# 10-RJ45_Protection.net
KiCad netlist of a schematic drawn in Altium Designer
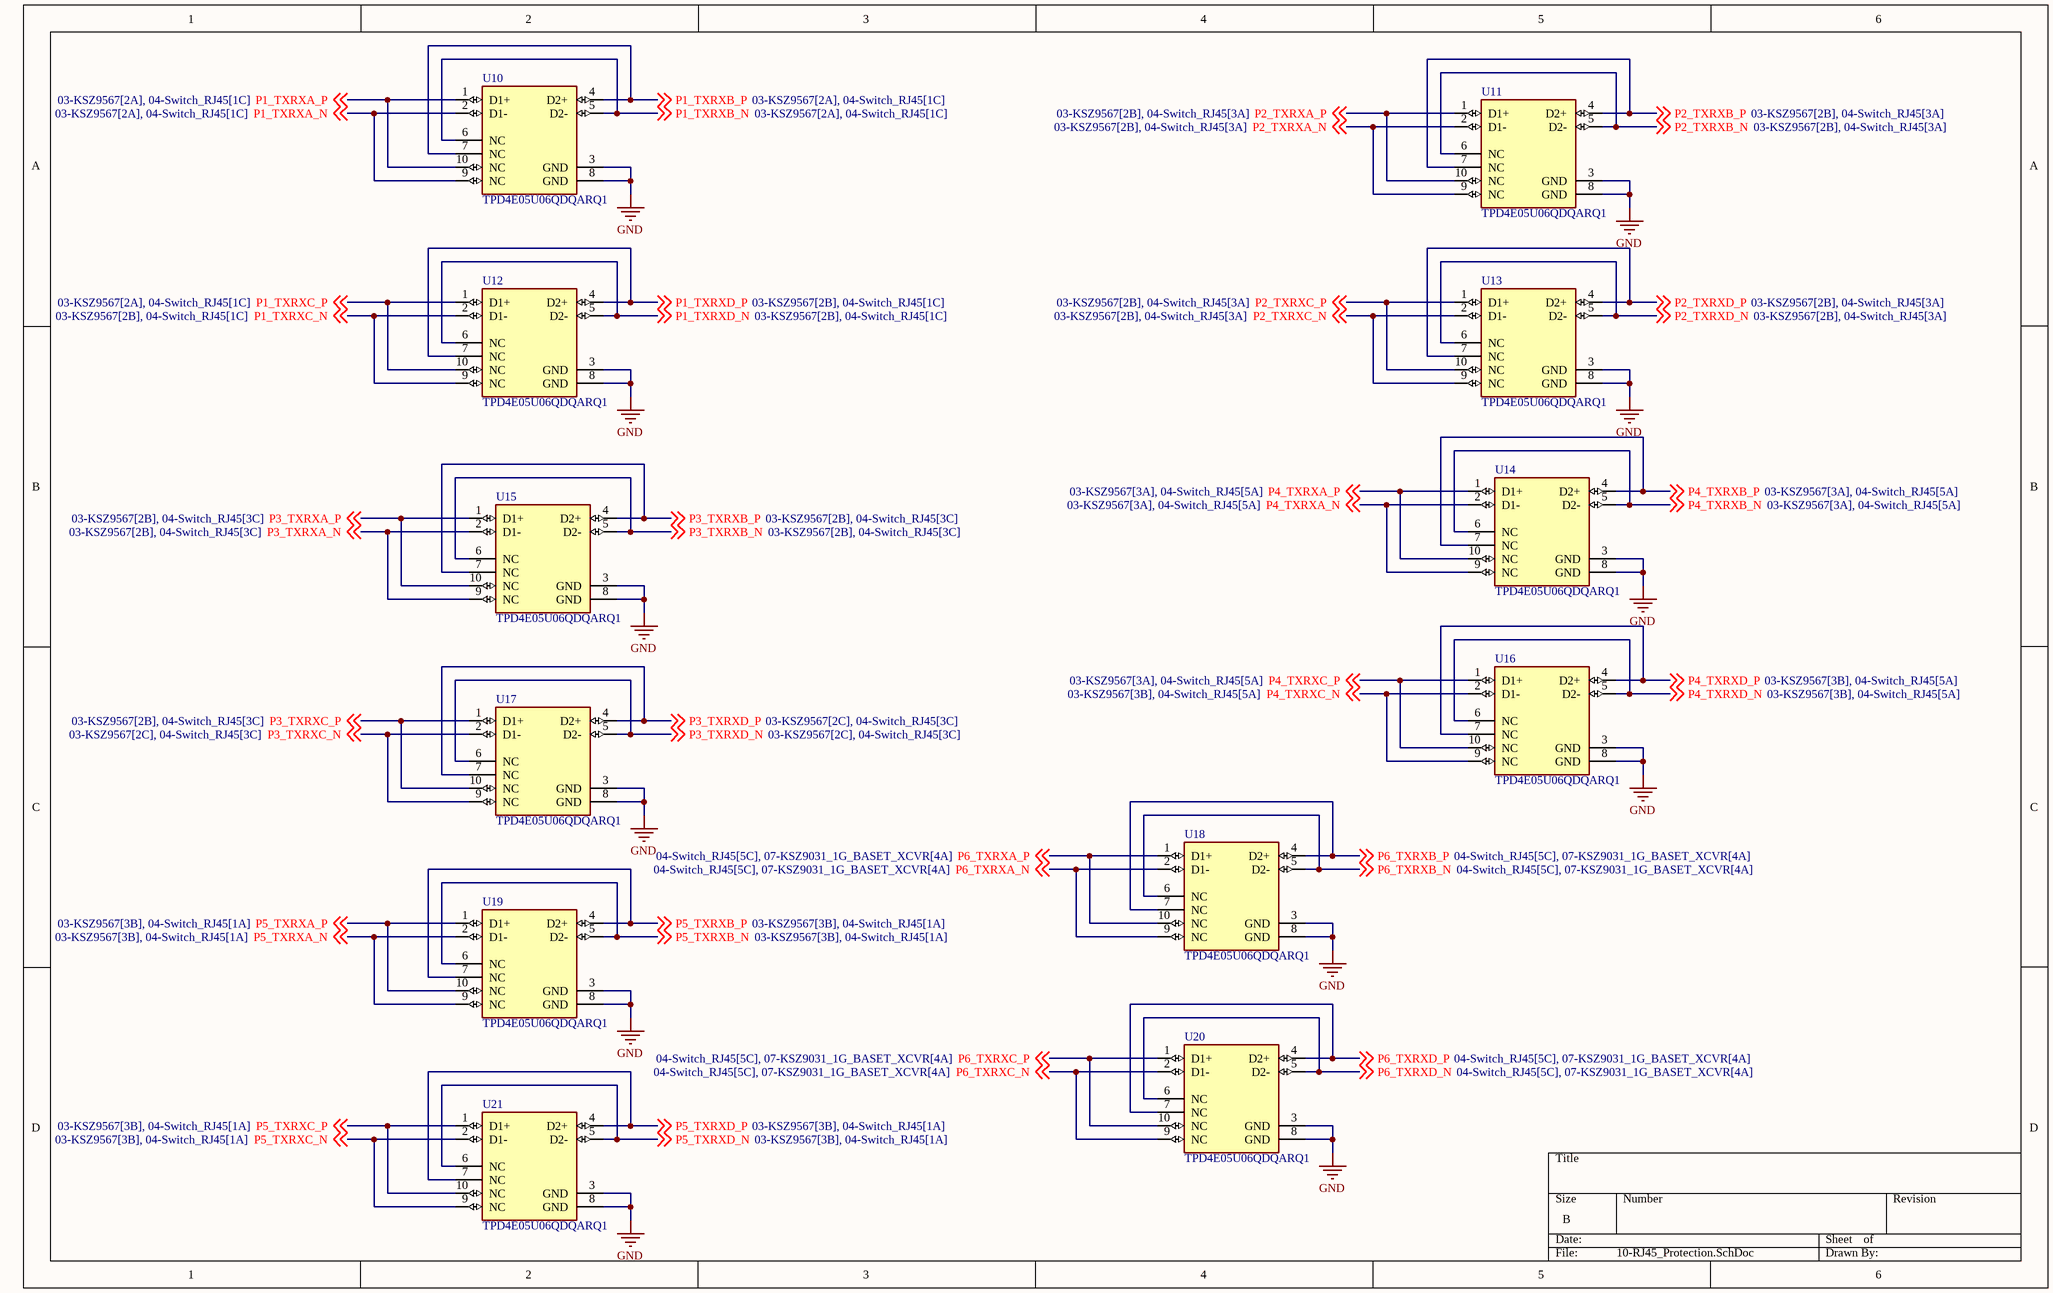
[diagram p0: 10-RJ45_Protection.SchDoc]

(export (version "E")
  (design (tool "Eeschema 10.0.6"))
  (components
    (comp (ref "U10")
      (value "TPD4E05U06QDQARQ1")
      (footprint "FP-DQA0010A-MFG")
      (description "TVS DIODE 5.5V 14V 10USON")
      (fields
        (field (name "OCTOPART") "https://octopart.com/tpd4e05u06qdqarq1-texas+instruments-48523459")
        (field (name "MANUFACTURER") "Texas Instruments")
      )
      (libsource (lib "Altium Content Vault") (part "f11f7ff102fa2b028e1355c732c836d"))
    )
    (comp (ref "U11")
      (value "TPD4E05U06QDQARQ1")
      (footprint "FP-DQA0010A-MFG")
      (description "TVS DIODE 5.5V 14V 10USON")
      (fields
        (field (name "OCTOPART") "https://octopart.com/tpd4e05u06qdqarq1-texas+instruments-48523459")
        (field (name "MANUFACTURER") "Texas Instruments")
      )
      (libsource (lib "Altium Content Vault") (part "f11f7ff102fa2b028e1355c732c836d"))
    )
    (comp (ref "U12")
      (value "TPD4E05U06QDQARQ1")
      (footprint "FP-DQA0010A-MFG")
      (description "TVS DIODE 5.5V 14V 10USON")
      (fields
        (field (name "OCTOPART") "https://octopart.com/tpd4e05u06qdqarq1-texas+instruments-48523459")
        (field (name "MANUFACTURER") "Texas Instruments")
      )
      (libsource (lib "Altium Content Vault") (part "f11f7ff102fa2b028e1355c732c836d"))
    )
    (comp (ref "U13")
      (value "TPD4E05U06QDQARQ1")
      (footprint "FP-DQA0010A-MFG")
      (description "TVS DIODE 5.5V 14V 10USON")
      (fields
        (field (name "OCTOPART") "https://octopart.com/tpd4e05u06qdqarq1-texas+instruments-48523459")
        (field (name "MANUFACTURER") "Texas Instruments")
      )
      (libsource (lib "Altium Content Vault") (part "f11f7ff102fa2b028e1355c732c836d"))
    )
    (comp (ref "U14")
      (value "TPD4E05U06QDQARQ1")
      (footprint "FP-DQA0010A-MFG")
      (description "TVS DIODE 5.5V 14V 10USON")
      (fields
        (field (name "OCTOPART") "https://octopart.com/tpd4e05u06qdqarq1-texas+instruments-48523459")
        (field (name "MANUFACTURER") "Texas Instruments")
      )
      (libsource (lib "Altium Content Vault") (part "f11f7ff102fa2b028e1355c732c836d"))
    )
    (comp (ref "U15")
      (value "TPD4E05U06QDQARQ1")
      (footprint "FP-DQA0010A-MFG")
      (description "TVS DIODE 5.5V 14V 10USON")
      (fields
        (field (name "OCTOPART") "https://octopart.com/tpd4e05u06qdqarq1-texas+instruments-48523459")
        (field (name "MANUFACTURER") "Texas Instruments")
      )
      (libsource (lib "Altium Content Vault") (part "f11f7ff102fa2b028e1355c732c836d"))
    )
    (comp (ref "U16")
      (value "TPD4E05U06QDQARQ1")
      (footprint "FP-DQA0010A-MFG")
      (description "TVS DIODE 5.5V 14V 10USON")
      (fields
        (field (name "OCTOPART") "https://octopart.com/tpd4e05u06qdqarq1-texas+instruments-48523459")
        (field (name "MANUFACTURER") "Texas Instruments")
      )
      (libsource (lib "Altium Content Vault") (part "f11f7ff102fa2b028e1355c732c836d"))
    )
    (comp (ref "U17")
      (value "TPD4E05U06QDQARQ1")
      (footprint "FP-DQA0010A-MFG")
      (description "TVS DIODE 5.5V 14V 10USON")
      (fields
        (field (name "OCTOPART") "https://octopart.com/tpd4e05u06qdqarq1-texas+instruments-48523459")
        (field (name "MANUFACTURER") "Texas Instruments")
      )
      (libsource (lib "Altium Content Vault") (part "f11f7ff102fa2b028e1355c732c836d"))
    )
    (comp (ref "U18")
      (value "TPD4E05U06QDQARQ1")
      (footprint "FP-DQA0010A-MFG")
      (description "TVS DIODE 5.5V 14V 10USON")
      (fields
        (field (name "OCTOPART") "https://octopart.com/tpd4e05u06qdqarq1-texas+instruments-48523459")
        (field (name "MANUFACTURER") "Texas Instruments")
      )
      (libsource (lib "Altium Content Vault") (part "f11f7ff102fa2b028e1355c732c836d"))
    )
    (comp (ref "U19")
      (value "TPD4E05U06QDQARQ1")
      (footprint "FP-DQA0010A-MFG")
      (description "TVS DIODE 5.5V 14V 10USON")
      (fields
        (field (name "OCTOPART") "https://octopart.com/tpd4e05u06qdqarq1-texas+instruments-48523459")
        (field (name "MANUFACTURER") "Texas Instruments")
      )
      (libsource (lib "Altium Content Vault") (part "f11f7ff102fa2b028e1355c732c836d"))
    )
    (comp (ref "U20")
      (value "TPD4E05U06QDQARQ1")
      (footprint "FP-DQA0010A-MFG")
      (description "TVS DIODE 5.5V 14V 10USON")
      (fields
        (field (name "OCTOPART") "https://octopart.com/tpd4e05u06qdqarq1-texas+instruments-48523459")
        (field (name "MANUFACTURER") "Texas Instruments")
      )
      (libsource (lib "Altium Content Vault") (part "f11f7ff102fa2b028e1355c732c836d"))
    )
    (comp (ref "U21")
      (value "TPD4E05U06QDQARQ1")
      (footprint "FP-DQA0010A-MFG")
      (description "TVS DIODE 5.5V 14V 10USON")
      (fields
        (field (name "OCTOPART") "https://octopart.com/tpd4e05u06qdqarq1-texas+instruments-48523459")
        (field (name "MANUFACTURER") "Texas Instruments")
      )
      (libsource (lib "Altium Content Vault") (part "f11f7ff102fa2b028e1355c732c836d"))
    )
  )
  (nets
    (net (code "1") (name "GND") (class "Default")
      (node (ref "U10") (pin "3") (pinfunction "GND_3") (pintype "power_in"))
      (node (ref "U10") (pin "8") (pinfunction "GND_8") (pintype "power_in"))
      (node (ref "U11") (pin "3") (pinfunction "GND_3") (pintype "power_in"))
      (node (ref "U11") (pin "8") (pinfunction "GND_8") (pintype "power_in"))
      (node (ref "U12") (pin "3") (pinfunction "GND_3") (pintype "power_in"))
      (node (ref "U12") (pin "8") (pinfunction "GND_8") (pintype "power_in"))
      (node (ref "U13") (pin "3") (pinfunction "GND_3") (pintype "power_in"))
      (node (ref "U13") (pin "8") (pinfunction "GND_8") (pintype "power_in"))
      (node (ref "U14") (pin "3") (pinfunction "GND_3") (pintype "power_in"))
      (node (ref "U14") (pin "8") (pinfunction "GND_8") (pintype "power_in"))
      (node (ref "U15") (pin "3") (pinfunction "GND_3") (pintype "power_in"))
      (node (ref "U15") (pin "8") (pinfunction "GND_8") (pintype "power_in"))
      (node (ref "U16") (pin "3") (pinfunction "GND_3") (pintype "power_in"))
      (node (ref "U16") (pin "8") (pinfunction "GND_8") (pintype "power_in"))
      (node (ref "U17") (pin "3") (pinfunction "GND_3") (pintype "power_in"))
      (node (ref "U17") (pin "8") (pinfunction "GND_8") (pintype "power_in"))
      (node (ref "U18") (pin "3") (pinfunction "GND_3") (pintype "power_in"))
      (node (ref "U18") (pin "8") (pinfunction "GND_8") (pintype "power_in"))
      (node (ref "U19") (pin "3") (pinfunction "GND_3") (pintype "power_in"))
      (node (ref "U19") (pin "8") (pinfunction "GND_8") (pintype "power_in"))
      (node (ref "U20") (pin "3") (pinfunction "GND_3") (pintype "power_in"))
      (node (ref "U20") (pin "8") (pinfunction "GND_8") (pintype "power_in"))
      (node (ref "U21") (pin "3") (pinfunction "GND_3") (pintype "power_in"))
      (node (ref "U21") (pin "8") (pinfunction "GND_8") (pintype "power_in"))
    )
    (net (code "2") (name "P1_TXRXA_N") (class "Default")
      (node (ref "U10") (pin "2") (pinfunction "D1-_2") (pintype "bidirectional"))
      (node (ref "U10") (pin "9") (pinfunction "NC_9") (pintype "bidirectional"))
    )
    (net (code "3") (name "P1_TXRXA_P") (class "Default")
      (node (ref "U10") (pin "1") (pinfunction "D1+_1") (pintype "bidirectional"))
      (node (ref "U10") (pin "10") (pinfunction "NC_10") (pintype "bidirectional"))
    )
    (net (code "4") (name "P1_TXRXB_N") (class "Default")
      (node (ref "U10") (pin "5") (pinfunction "D2-_5") (pintype "bidirectional"))
      (node (ref "U10") (pin "6") (pinfunction "NC_6") (pintype "passive"))
    )
    (net (code "5") (name "P1_TXRXB_P") (class "Default")
      (node (ref "U10") (pin "4") (pinfunction "D2+_4") (pintype "bidirectional"))
      (node (ref "U10") (pin "7") (pinfunction "NC_7") (pintype "passive"))
    )
    (net (code "6") (name "P1_TXRXC_N") (class "Default")
      (node (ref "U12") (pin "2") (pinfunction "D1-_2") (pintype "bidirectional"))
      (node (ref "U12") (pin "9") (pinfunction "NC_9") (pintype "bidirectional"))
    )
    (net (code "7") (name "P1_TXRXC_P") (class "Default")
      (node (ref "U12") (pin "1") (pinfunction "D1+_1") (pintype "bidirectional"))
      (node (ref "U12") (pin "10") (pinfunction "NC_10") (pintype "bidirectional"))
    )
    (net (code "8") (name "P1_TXRXD_N") (class "Default")
      (node (ref "U12") (pin "5") (pinfunction "D2-_5") (pintype "bidirectional"))
      (node (ref "U12") (pin "6") (pinfunction "NC_6") (pintype "passive"))
    )
    (net (code "9") (name "P1_TXRXD_P") (class "Default")
      (node (ref "U12") (pin "4") (pinfunction "D2+_4") (pintype "bidirectional"))
      (node (ref "U12") (pin "7") (pinfunction "NC_7") (pintype "passive"))
    )
    (net (code "10") (name "P2_TXRXA_N") (class "Default")
      (node (ref "U11") (pin "2") (pinfunction "D1-_2") (pintype "bidirectional"))
      (node (ref "U11") (pin "9") (pinfunction "NC_9") (pintype "bidirectional"))
    )
    (net (code "11") (name "P2_TXRXA_P") (class "Default")
      (node (ref "U11") (pin "1") (pinfunction "D1+_1") (pintype "bidirectional"))
      (node (ref "U11") (pin "10") (pinfunction "NC_10") (pintype "bidirectional"))
    )
    (net (code "12") (name "P2_TXRXB_N") (class "Default")
      (node (ref "U11") (pin "5") (pinfunction "D2-_5") (pintype "bidirectional"))
      (node (ref "U11") (pin "6") (pinfunction "NC_6") (pintype "passive"))
    )
    (net (code "13") (name "P2_TXRXB_P") (class "Default")
      (node (ref "U11") (pin "4") (pinfunction "D2+_4") (pintype "bidirectional"))
      (node (ref "U11") (pin "7") (pinfunction "NC_7") (pintype "passive"))
    )
    (net (code "14") (name "P2_TXRXC_N") (class "Default")
      (node (ref "U13") (pin "2") (pinfunction "D1-_2") (pintype "bidirectional"))
      (node (ref "U13") (pin "9") (pinfunction "NC_9") (pintype "bidirectional"))
    )
    (net (code "15") (name "P2_TXRXC_P") (class "Default")
      (node (ref "U13") (pin "1") (pinfunction "D1+_1") (pintype "bidirectional"))
      (node (ref "U13") (pin "10") (pinfunction "NC_10") (pintype "bidirectional"))
    )
    (net (code "16") (name "P2_TXRXD_N") (class "Default")
      (node (ref "U13") (pin "5") (pinfunction "D2-_5") (pintype "bidirectional"))
      (node (ref "U13") (pin "6") (pinfunction "NC_6") (pintype "passive"))
    )
    (net (code "17") (name "P2_TXRXD_P") (class "Default")
      (node (ref "U13") (pin "4") (pinfunction "D2+_4") (pintype "bidirectional"))
      (node (ref "U13") (pin "7") (pinfunction "NC_7") (pintype "passive"))
    )
    (net (code "18") (name "P3_TXRXA_N") (class "Default")
      (node (ref "U15") (pin "2") (pinfunction "D1-_2") (pintype "bidirectional"))
      (node (ref "U15") (pin "9") (pinfunction "NC_9") (pintype "bidirectional"))
    )
    (net (code "19") (name "P3_TXRXA_P") (class "Default")
      (node (ref "U15") (pin "1") (pinfunction "D1+_1") (pintype "bidirectional"))
      (node (ref "U15") (pin "10") (pinfunction "NC_10") (pintype "bidirectional"))
    )
    (net (code "20") (name "P3_TXRXB_N") (class "Default")
      (node (ref "U15") (pin "5") (pinfunction "D2-_5") (pintype "bidirectional"))
      (node (ref "U15") (pin "6") (pinfunction "NC_6") (pintype "passive"))
    )
    (net (code "21") (name "P3_TXRXB_P") (class "Default")
      (node (ref "U15") (pin "4") (pinfunction "D2+_4") (pintype "bidirectional"))
      (node (ref "U15") (pin "7") (pinfunction "NC_7") (pintype "passive"))
    )
    (net (code "22") (name "P3_TXRXC_N") (class "Default")
      (node (ref "U17") (pin "2") (pinfunction "D1-_2") (pintype "bidirectional"))
      (node (ref "U17") (pin "9") (pinfunction "NC_9") (pintype "bidirectional"))
    )
    (net (code "23") (name "P3_TXRXC_P") (class "Default")
      (node (ref "U17") (pin "1") (pinfunction "D1+_1") (pintype "bidirectional"))
      (node (ref "U17") (pin "10") (pinfunction "NC_10") (pintype "bidirectional"))
    )
    (net (code "24") (name "P3_TXRXD_N") (class "Default")
      (node (ref "U17") (pin "5") (pinfunction "D2-_5") (pintype "bidirectional"))
      (node (ref "U17") (pin "6") (pinfunction "NC_6") (pintype "passive"))
    )
    (net (code "25") (name "P3_TXRXD_P") (class "Default")
      (node (ref "U17") (pin "4") (pinfunction "D2+_4") (pintype "bidirectional"))
      (node (ref "U17") (pin "7") (pinfunction "NC_7") (pintype "passive"))
    )
    (net (code "26") (name "P4_TXRXA_N") (class "Default")
      (node (ref "U14") (pin "2") (pinfunction "D1-_2") (pintype "bidirectional"))
      (node (ref "U14") (pin "9") (pinfunction "NC_9") (pintype "bidirectional"))
    )
    (net (code "27") (name "P4_TXRXA_P") (class "Default")
      (node (ref "U14") (pin "1") (pinfunction "D1+_1") (pintype "bidirectional"))
      (node (ref "U14") (pin "10") (pinfunction "NC_10") (pintype "bidirectional"))
    )
    (net (code "28") (name "P4_TXRXB_N") (class "Default")
      (node (ref "U14") (pin "5") (pinfunction "D2-_5") (pintype "bidirectional"))
      (node (ref "U14") (pin "6") (pinfunction "NC_6") (pintype "passive"))
    )
    (net (code "29") (name "P4_TXRXB_P") (class "Default")
      (node (ref "U14") (pin "4") (pinfunction "D2+_4") (pintype "bidirectional"))
      (node (ref "U14") (pin "7") (pinfunction "NC_7") (pintype "passive"))
    )
    (net (code "30") (name "P4_TXRXC_N") (class "Default")
      (node (ref "U16") (pin "2") (pinfunction "D1-_2") (pintype "bidirectional"))
      (node (ref "U16") (pin "9") (pinfunction "NC_9") (pintype "bidirectional"))
    )
    (net (code "31") (name "P4_TXRXC_P") (class "Default")
      (node (ref "U16") (pin "1") (pinfunction "D1+_1") (pintype "bidirectional"))
      (node (ref "U16") (pin "10") (pinfunction "NC_10") (pintype "bidirectional"))
    )
    (net (code "32") (name "P4_TXRXD_N") (class "Default")
      (node (ref "U16") (pin "5") (pinfunction "D2-_5") (pintype "bidirectional"))
      (node (ref "U16") (pin "6") (pinfunction "NC_6") (pintype "passive"))
    )
    (net (code "33") (name "P4_TXRXD_P") (class "Default")
      (node (ref "U16") (pin "4") (pinfunction "D2+_4") (pintype "bidirectional"))
      (node (ref "U16") (pin "7") (pinfunction "NC_7") (pintype "passive"))
    )
    (net (code "34") (name "P5_TXRXA_N") (class "Default")
      (node (ref "U19") (pin "2") (pinfunction "D1-_2") (pintype "bidirectional"))
      (node (ref "U19") (pin "9") (pinfunction "NC_9") (pintype "bidirectional"))
    )
    (net (code "35") (name "P5_TXRXA_P") (class "Default")
      (node (ref "U19") (pin "1") (pinfunction "D1+_1") (pintype "bidirectional"))
      (node (ref "U19") (pin "10") (pinfunction "NC_10") (pintype "bidirectional"))
    )
    (net (code "36") (name "P5_TXRXB_N") (class "Default")
      (node (ref "U19") (pin "5") (pinfunction "D2-_5") (pintype "bidirectional"))
      (node (ref "U19") (pin "6") (pinfunction "NC_6") (pintype "passive"))
    )
    (net (code "37") (name "P5_TXRXB_P") (class "Default")
      (node (ref "U19") (pin "4") (pinfunction "D2+_4") (pintype "bidirectional"))
      (node (ref "U19") (pin "7") (pinfunction "NC_7") (pintype "passive"))
    )
    (net (code "38") (name "P5_TXRXC_N") (class "Default")
      (node (ref "U21") (pin "2") (pinfunction "D1-_2") (pintype "bidirectional"))
      (node (ref "U21") (pin "9") (pinfunction "NC_9") (pintype "bidirectional"))
    )
    (net (code "39") (name "P5_TXRXC_P") (class "Default")
      (node (ref "U21") (pin "1") (pinfunction "D1+_1") (pintype "bidirectional"))
      (node (ref "U21") (pin "10") (pinfunction "NC_10") (pintype "bidirectional"))
    )
    (net (code "40") (name "P5_TXRXD_N") (class "Default")
      (node (ref "U21") (pin "5") (pinfunction "D2-_5") (pintype "bidirectional"))
      (node (ref "U21") (pin "6") (pinfunction "NC_6") (pintype "passive"))
    )
    (net (code "41") (name "P5_TXRXD_P") (class "Default")
      (node (ref "U21") (pin "4") (pinfunction "D2+_4") (pintype "bidirectional"))
      (node (ref "U21") (pin "7") (pinfunction "NC_7") (pintype "passive"))
    )
    (net (code "42") (name "P6_TXRXA_N") (class "Default")
      (node (ref "U18") (pin "2") (pinfunction "D1-_2") (pintype "bidirectional"))
      (node (ref "U18") (pin "9") (pinfunction "NC_9") (pintype "bidirectional"))
    )
    (net (code "43") (name "P6_TXRXA_P") (class "Default")
      (node (ref "U18") (pin "1") (pinfunction "D1+_1") (pintype "bidirectional"))
      (node (ref "U18") (pin "10") (pinfunction "NC_10") (pintype "bidirectional"))
    )
    (net (code "44") (name "P6_TXRXB_N") (class "Default")
      (node (ref "U18") (pin "5") (pinfunction "D2-_5") (pintype "bidirectional"))
      (node (ref "U18") (pin "6") (pinfunction "NC_6") (pintype "passive"))
    )
    (net (code "45") (name "P6_TXRXB_P") (class "Default")
      (node (ref "U18") (pin "4") (pinfunction "D2+_4") (pintype "bidirectional"))
      (node (ref "U18") (pin "7") (pinfunction "NC_7") (pintype "passive"))
    )
    (net (code "46") (name "P6_TXRXC_N") (class "Default")
      (node (ref "U20") (pin "2") (pinfunction "D1-_2") (pintype "bidirectional"))
      (node (ref "U20") (pin "9") (pinfunction "NC_9") (pintype "bidirectional"))
    )
    (net (code "47") (name "P6_TXRXC_P") (class "Default")
      (node (ref "U20") (pin "1") (pinfunction "D1+_1") (pintype "bidirectional"))
      (node (ref "U20") (pin "10") (pinfunction "NC_10") (pintype "bidirectional"))
    )
    (net (code "48") (name "P6_TXRXD_N") (class "Default")
      (node (ref "U20") (pin "5") (pinfunction "D2-_5") (pintype "bidirectional"))
      (node (ref "U20") (pin "6") (pinfunction "NC_6") (pintype "passive"))
    )
    (net (code "49") (name "P6_TXRXD_P") (class "Default")
      (node (ref "U20") (pin "4") (pinfunction "D2+_4") (pintype "bidirectional"))
      (node (ref "U20") (pin "7") (pinfunction "NC_7") (pintype "passive"))
    )
  )
)
